# Motor3.net
KiCad netlist of a schematic drawn in Altium Designer
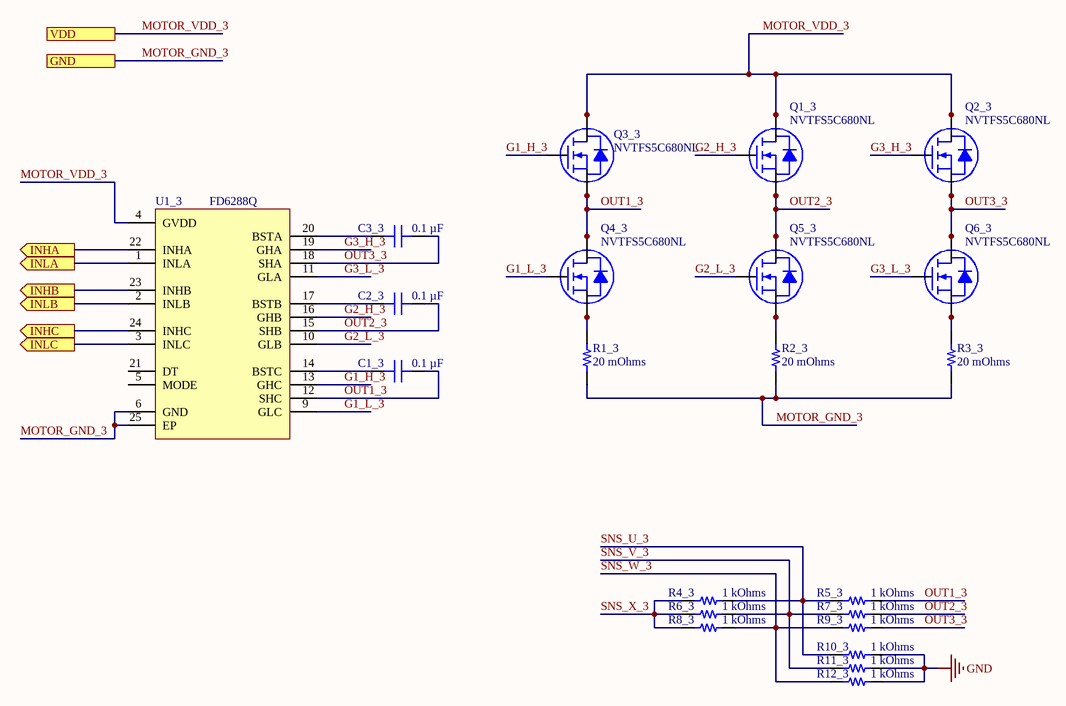
[diagram p0: Motor3.SchDoc]

(export (version "E")
  (design (tool "Eeschema 10.0.6"))
  (components
    (comp (ref "C1_3")
      (value "0.1 µF")
      (footprint "CAP 0402_1005")
      (description "CAP CER 0.1UF 16V X7R 0402")
      (fields (field (name "PART NUMBER") "C0402C104K4RACAUTO") (field (name "MANUFACTURER") "KEMET"))
      (libsource (lib "Celestial Altium Library - altium_library") (part "Capacitor"))
    )
    (comp (ref "C2_3")
      (value "0.1 µF")
      (footprint "CAP 0402_1005")
      (description "CAP CER 0.1UF 16V X7R 0402")
      (fields (field (name "PART NUMBER") "C0402C104K4RACAUTO") (field (name "MANUFACTURER") "KEMET"))
      (libsource (lib "Celestial Altium Library - altium_library") (part "Capacitor"))
    )
    (comp (ref "C3_3")
      (value "0.1 µF")
      (footprint "CAP 0402_1005")
      (description "CAP CER 0.1UF 16V X7R 0402")
      (fields (field (name "PART NUMBER") "C0402C104K4RACAUTO") (field (name "MANUFACTURER") "KEMET"))
      (libsource (lib "Celestial Altium Library - altium_library") (part "Capacitor"))
    )
    (comp (ref "Q1_3")
      (value "NVTFS5C680NL")
      (footprint "NVTFS015N04CTAG")
      (description "N-FET")
      (libsource (lib "IC") (part "NVTFS5C680NL"))
    )
    (comp (ref "Q2_3")
      (value "NVTFS5C680NL")
      (footprint "NVTFS015N04CTAG")
      (description "N-FET")
      (libsource (lib "IC") (part "NVTFS5C680NL"))
    )
    (comp (ref "Q3_3")
      (value "NVTFS5C680NL")
      (footprint "NVTFS015N04CTAG")
      (description "N-FET")
      (libsource (lib "IC") (part "NVTFS5C680NL"))
    )
    (comp (ref "Q4_3")
      (value "NVTFS5C680NL")
      (footprint "NVTFS015N04CTAG")
      (description "N-FET")
      (libsource (lib "IC") (part "NVTFS5C680NL"))
    )
    (comp (ref "Q5_3")
      (value "NVTFS5C680NL")
      (footprint "NVTFS015N04CTAG")
      (description "N-FET")
      (libsource (lib "IC") (part "NVTFS5C680NL"))
    )
    (comp (ref "Q6_3")
      (value "NVTFS5C680NL")
      (footprint "NVTFS015N04CTAG")
      (description "N-FET")
      (libsource (lib "IC") (part "NVTFS5C680NL"))
    )
    (comp (ref "R1_3")
      (value "20 mOhms")
      (footprint "STACKPOLE CSR0805")
      (description "RES 0.02 OHM 1% 1/3W 0603")
      (fields
        (field (name "PART NUMBER") "ERJ-3BWFR020V")
        (field (name "MANUFACTURER") "Panasonic Electronic Components")
      )
      (libsource (lib "Celestial Altium Library - altium_library") (part "Resistor"))
    )
    (comp (ref "R2_3")
      (value "20 mOhms")
      (footprint "STACKPOLE CSR0805")
      (description "RES 0.02 OHM 1% 1/3W 0603")
      (fields
        (field (name "PART NUMBER") "ERJ-3BWFR020V")
        (field (name "MANUFACTURER") "Panasonic Electronic Components")
      )
      (libsource (lib "Celestial Altium Library - altium_library") (part "Resistor"))
    )
    (comp (ref "R3_3")
      (value "20 mOhms")
      (footprint "STACKPOLE CSR0805")
      (description "RES 0.02 OHM 1% 1/3W 0603")
      (fields
        (field (name "PART NUMBER") "ERJ-3BWFR020V")
        (field (name "MANUFACTURER") "Panasonic Electronic Components")
      )
      (libsource (lib "Celestial Altium Library - altium_library") (part "Resistor"))
    )
    (comp (ref "R4_3")
      (value "1 kOhms")
      (footprint "RES 0402_1005")
      (description "RES 14.3K OHM 1% 1/10W 0402")
      (fields
        (field (name "PART NUMBER") "RK73H1ETTP1432F")
        (field (name "MANUFACTURER") "KOA Speer Electronics, Inc.")
      )
      (libsource (lib "Celestial Altium Library - altium_library") (part "Resistor"))
    )
    (comp (ref "R5_3")
      (value "1 kOhms")
      (footprint "RES 0402_1005")
      (description "RES 14.3K OHM 1% 1/10W 0402")
      (fields
        (field (name "PART NUMBER") "RK73H1ETTP1432F")
        (field (name "MANUFACTURER") "KOA Speer Electronics, Inc.")
      )
      (libsource (lib "Celestial Altium Library - altium_library") (part "Resistor"))
    )
    (comp (ref "R6_3")
      (value "1 kOhms")
      (footprint "RES 0402_1005")
      (description "RES 14.3K OHM 1% 1/10W 0402")
      (fields
        (field (name "PART NUMBER") "RK73H1ETTP1432F")
        (field (name "MANUFACTURER") "KOA Speer Electronics, Inc.")
      )
      (libsource (lib "Celestial Altium Library - altium_library") (part "Resistor"))
    )
    (comp (ref "R7_3")
      (value "1 kOhms")
      (footprint "RES 0402_1005")
      (description "RES 14.3K OHM 1% 1/10W 0402")
      (fields
        (field (name "PART NUMBER") "RK73H1ETTP1432F")
        (field (name "MANUFACTURER") "KOA Speer Electronics, Inc.")
      )
      (libsource (lib "Celestial Altium Library - altium_library") (part "Resistor"))
    )
    (comp (ref "R8_3")
      (value "1 kOhms")
      (footprint "RES 0402_1005")
      (description "RES 14.3K OHM 1% 1/10W 0402")
      (fields
        (field (name "PART NUMBER") "RK73H1ETTP1432F")
        (field (name "MANUFACTURER") "KOA Speer Electronics, Inc.")
      )
      (libsource (lib "Celestial Altium Library - altium_library") (part "Resistor"))
    )
    (comp (ref "R9_3")
      (value "1 kOhms")
      (footprint "RES 0402_1005")
      (description "RES 14.3K OHM 1% 1/10W 0402")
      (fields
        (field (name "PART NUMBER") "RK73H1ETTP1432F")
        (field (name "MANUFACTURER") "KOA Speer Electronics, Inc.")
      )
      (libsource (lib "Celestial Altium Library - altium_library") (part "Resistor"))
    )
    (comp (ref "R10_3")
      (value "1 kOhms")
      (footprint "RES 0402_1005")
      (description "RES 14.3K OHM 1% 1/10W 0402")
      (fields
        (field (name "PART NUMBER") "RK73H1ETTP1432F")
        (field (name "MANUFACTURER") "KOA Speer Electronics, Inc.")
      )
      (libsource (lib "Celestial Altium Library - altium_library") (part "Resistor"))
    )
    (comp (ref "R11_3")
      (value "1 kOhms")
      (footprint "RES 0402_1005")
      (description "RES 14.3K OHM 1% 1/10W 0402")
      (fields
        (field (name "PART NUMBER") "RK73H1ETTP1432F")
        (field (name "MANUFACTURER") "KOA Speer Electronics, Inc.")
      )
      (libsource (lib "Celestial Altium Library - altium_library") (part "Resistor"))
    )
    (comp (ref "R12_3")
      (value "1 kOhms")
      (footprint "RES 0402_1005")
      (description "RES 14.3K OHM 1% 1/10W 0402")
      (fields
        (field (name "PART NUMBER") "RK73H1ETTP1432F")
        (field (name "MANUFACTURER") "KOA Speer Electronics, Inc.")
      )
      (libsource (lib "Celestial Altium Library - altium_library") (part "Resistor"))
    )
    (comp (ref "U1_3")
      (value "FD6288Q")
      (footprint "QFN50P400X400X100-25N")
      (description "3 Phase Gate Driver 1.5-2.2A")
      (fields (field (name "MF") "Texas Instruments") (field (name "MP") "UCC27282DRCR"))
      (libsource (lib "IC") (part "FD6288Q"))
    )
  )
  (nets
    (net (code "1") (name "/G1_H_3") (class "Default")
      (node (ref "Q3_3") (pin "4") (pinfunction "G_4") (pintype "passive"))
      (node (ref "U1_3") (pin "13") (pinfunction "GHC_13") (pintype "passive"))
    )
    (net (code "2") (name "/G1_L_3") (class "Default")
      (node (ref "Q4_3") (pin "4") (pinfunction "G_4") (pintype "passive"))
      (node (ref "U1_3") (pin "9") (pinfunction "GLC_9") (pintype "passive"))
    )
    (net (code "3") (name "/G2_H_3") (class "Default")
      (node (ref "Q1_3") (pin "4") (pinfunction "G_4") (pintype "passive"))
      (node (ref "U1_3") (pin "16") (pinfunction "GHB_16") (pintype "passive"))
    )
    (net (code "4") (name "/G2_L_3") (class "Default")
      (node (ref "Q5_3") (pin "4") (pinfunction "G_4") (pintype "passive"))
      (node (ref "U1_3") (pin "10") (pinfunction "GLB_10") (pintype "passive"))
    )
    (net (code "5") (name "/G3_H_3") (class "Default")
      (node (ref "Q2_3") (pin "4") (pinfunction "G_4") (pintype "passive"))
      (node (ref "U1_3") (pin "19") (pinfunction "GHA_19") (pintype "passive"))
    )
    (net (code "6") (name "/G3_L_3") (class "Default")
      (node (ref "Q6_3") (pin "4") (pinfunction "G_4") (pintype "passive"))
      (node (ref "U1_3") (pin "11") (pinfunction "GLA_11") (pintype "passive"))
    )
    (net (code "7") (name "/INHA") (class "Default")
      (node (ref "U1_3") (pin "22") (pinfunction "INHA_22") (pintype "passive"))
    )
    (net (code "8") (name "/INHB") (class "Default")
      (node (ref "U1_3") (pin "23") (pinfunction "INHB_23") (pintype "passive"))
    )
    (net (code "9") (name "/INHC") (class "Default")
      (node (ref "U1_3") (pin "24") (pinfunction "INHC_24") (pintype "passive"))
    )
    (net (code "10") (name "/INLA") (class "Default")
      (node (ref "U1_3") (pin "1") (pinfunction "INLA_1") (pintype "passive"))
    )
    (net (code "11") (name "/INLB") (class "Default")
      (node (ref "U1_3") (pin "2") (pinfunction "INLB_2") (pintype "passive"))
    )
    (net (code "12") (name "/INLC") (class "Default")
      (node (ref "U1_3") (pin "3") (pinfunction "INLC_3") (pintype "passive"))
    )
    (net (code "13") (name "/MOTOR_VDD_3") (class "Default")
      (node (ref "Q1_3") (pin "5") (pinfunction "D_5") (pintype "passive"))
      (node (ref "Q1_3") (pin "6") (pinfunction "D_6") (pintype "passive"))
      (node (ref "Q1_3") (pin "7") (pinfunction "D_7") (pintype "passive"))
      (node (ref "Q1_3") (pin "8") (pinfunction "D_8") (pintype "passive"))
      (node (ref "Q2_3") (pin "5") (pinfunction "D_5") (pintype "passive"))
      (node (ref "Q2_3") (pin "6") (pinfunction "D_6") (pintype "passive"))
      (node (ref "Q2_3") (pin "7") (pinfunction "D_7") (pintype "passive"))
      (node (ref "Q2_3") (pin "8") (pinfunction "D_8") (pintype "passive"))
      (node (ref "Q3_3") (pin "5") (pinfunction "D_5") (pintype "passive"))
      (node (ref "Q3_3") (pin "6") (pinfunction "D_6") (pintype "passive"))
      (node (ref "Q3_3") (pin "7") (pinfunction "D_7") (pintype "passive"))
      (node (ref "Q3_3") (pin "8") (pinfunction "D_8") (pintype "passive"))
      (node (ref "U1_3") (pin "4") (pinfunction "GVDD_4") (pintype "passive"))
    )
    (net (code "14") (name "/OUT1_3") (class "Default")
      (node (ref "C1_3") (pin "2") (pinfunction "2_2") (pintype "passive"))
      (node (ref "Q3_3") (pin "1") (pinfunction "S_1") (pintype "passive"))
      (node (ref "Q3_3") (pin "2") (pinfunction "S_2") (pintype "passive"))
      (node (ref "Q3_3") (pin "3") (pinfunction "S_3") (pintype "passive"))
      (node (ref "Q4_3") (pin "5") (pinfunction "D_5") (pintype "passive"))
      (node (ref "Q4_3") (pin "6") (pinfunction "D_6") (pintype "passive"))
      (node (ref "Q4_3") (pin "7") (pinfunction "D_7") (pintype "passive"))
      (node (ref "Q4_3") (pin "8") (pinfunction "D_8") (pintype "passive"))
      (node (ref "R5_3") (pin "2") (pinfunction "2_2") (pintype "passive"))
      (node (ref "U1_3") (pin "12") (pinfunction "SHC_12") (pintype "passive"))
    )
    (net (code "15") (name "/OUT2_3") (class "Default")
      (node (ref "C2_3") (pin "2") (pinfunction "2_2") (pintype "passive"))
      (node (ref "Q1_3") (pin "1") (pinfunction "S_1") (pintype "passive"))
      (node (ref "Q1_3") (pin "2") (pinfunction "S_2") (pintype "passive"))
      (node (ref "Q1_3") (pin "3") (pinfunction "S_3") (pintype "passive"))
      (node (ref "Q5_3") (pin "5") (pinfunction "D_5") (pintype "passive"))
      (node (ref "Q5_3") (pin "6") (pinfunction "D_6") (pintype "passive"))
      (node (ref "Q5_3") (pin "7") (pinfunction "D_7") (pintype "passive"))
      (node (ref "Q5_3") (pin "8") (pinfunction "D_8") (pintype "passive"))
      (node (ref "R7_3") (pin "2") (pinfunction "2_2") (pintype "passive"))
      (node (ref "U1_3") (pin "15") (pinfunction "SHB_15") (pintype "passive"))
    )
    (net (code "16") (name "/OUT3_3") (class "Default")
      (node (ref "C3_3") (pin "2") (pinfunction "2_2") (pintype "passive"))
      (node (ref "Q2_3") (pin "1") (pinfunction "S_1") (pintype "passive"))
      (node (ref "Q2_3") (pin "2") (pinfunction "S_2") (pintype "passive"))
      (node (ref "Q2_3") (pin "3") (pinfunction "S_3") (pintype "passive"))
      (node (ref "Q6_3") (pin "5") (pinfunction "D_5") (pintype "passive"))
      (node (ref "Q6_3") (pin "6") (pinfunction "D_6") (pintype "passive"))
      (node (ref "Q6_3") (pin "7") (pinfunction "D_7") (pintype "passive"))
      (node (ref "Q6_3") (pin "8") (pinfunction "D_8") (pintype "passive"))
      (node (ref "R9_3") (pin "2") (pinfunction "2_2") (pintype "passive"))
      (node (ref "U1_3") (pin "18") (pinfunction "SHA_18") (pintype "passive"))
    )
    (net (code "17") (name "/SNS_U_3") (class "Default")
      (node (ref "R10_3") (pin "2") (pinfunction "2_2") (pintype "passive"))
      (node (ref "R4_3") (pin "2") (pinfunction "2_2") (pintype "passive"))
      (node (ref "R5_3") (pin "1") (pinfunction "1_1") (pintype "passive"))
    )
    (net (code "18") (name "/SNS_V_3") (class "Default")
      (node (ref "R11_3") (pin "2") (pinfunction "2_2") (pintype "passive"))
      (node (ref "R6_3") (pin "2") (pinfunction "2_2") (pintype "passive"))
      (node (ref "R7_3") (pin "1") (pinfunction "1_1") (pintype "passive"))
    )
    (net (code "19") (name "/SNS_W_3") (class "Default")
      (node (ref "R12_3") (pin "2") (pinfunction "2_2") (pintype "passive"))
      (node (ref "R8_3") (pin "2") (pinfunction "2_2") (pintype "passive"))
      (node (ref "R9_3") (pin "1") (pinfunction "1_1") (pintype "passive"))
    )
    (net (code "20") (name "/SNS_X_3") (class "Default")
      (node (ref "R4_3") (pin "1") (pinfunction "1_1") (pintype "passive"))
      (node (ref "R6_3") (pin "1") (pinfunction "1_1") (pintype "passive"))
      (node (ref "R8_3") (pin "1") (pinfunction "1_1") (pintype "passive"))
    )
    (net (code "21") (name "GND") (class "Default")
      (node (ref "R10_3") (pin "1") (pinfunction "1_1") (pintype "passive"))
      (node (ref "R11_3") (pin "1") (pinfunction "1_1") (pintype "passive"))
      (node (ref "R12_3") (pin "1") (pinfunction "1_1") (pintype "passive"))
      (node (ref "R1_3") (pin "1") (pinfunction "1_1") (pintype "passive"))
      (node (ref "R2_3") (pin "1") (pinfunction "1_1") (pintype "passive"))
      (node (ref "R3_3") (pin "1") (pinfunction "1_1") (pintype "passive"))
      (node (ref "U1_3") (pin "25") (pinfunction "EP_25") (pintype "passive"))
      (node (ref "U1_3") (pin "6") (pinfunction "GND_6") (pintype "passive"))
    )
    (net (code "22") (name "Net-(Q4_3-S-Pad1)") (class "Default")
      (node (ref "Q4_3") (pin "1") (pinfunction "S_1") (pintype "passive"))
      (node (ref "Q4_3") (pin "2") (pinfunction "S_2") (pintype "passive"))
      (node (ref "Q4_3") (pin "3") (pinfunction "S_3") (pintype "passive"))
      (node (ref "R1_3") (pin "2") (pinfunction "2_2") (pintype "passive"))
    )
    (net (code "23") (name "Net-(Q5_3-S-Pad1)") (class "Default")
      (node (ref "Q5_3") (pin "1") (pinfunction "S_1") (pintype "passive"))
      (node (ref "Q5_3") (pin "2") (pinfunction "S_2") (pintype "passive"))
      (node (ref "Q5_3") (pin "3") (pinfunction "S_3") (pintype "passive"))
      (node (ref "R2_3") (pin "2") (pinfunction "2_2") (pintype "passive"))
    )
    (net (code "24") (name "Net-(Q6_3-S-Pad1)") (class "Default")
      (node (ref "Q6_3") (pin "1") (pinfunction "S_1") (pintype "passive"))
      (node (ref "Q6_3") (pin "2") (pinfunction "S_2") (pintype "passive"))
      (node (ref "Q6_3") (pin "3") (pinfunction "S_3") (pintype "passive"))
      (node (ref "R3_3") (pin "2") (pinfunction "2_2") (pintype "passive"))
    )
    (net (code "25") (name "Net-(U1_3-BSTA)") (class "Default")
      (node (ref "C3_3") (pin "1") (pinfunction "1_1") (pintype "passive"))
      (node (ref "U1_3") (pin "20") (pinfunction "BSTA_20") (pintype "passive"))
    )
    (net (code "26") (name "Net-(U1_3-BSTB)") (class "Default")
      (node (ref "C2_3") (pin "1") (pinfunction "1_1") (pintype "passive"))
      (node (ref "U1_3") (pin "17") (pinfunction "BSTB_17") (pintype "passive"))
    )
    (net (code "27") (name "Net-(U1_3-BSTC)") (class "Default")
      (node (ref "C1_3") (pin "1") (pinfunction "1_1") (pintype "passive"))
      (node (ref "U1_3") (pin "14") (pinfunction "BSTC_14") (pintype "passive"))
    )
    (net (code "28") (name "unconnected-(U1_3-DT-Pad21)") (class "Default")
      (node (ref "U1_3") (pin "21") (pinfunction "DT_21") (pintype "passive"))
    )
    (net (code "29") (name "unconnected-(U1_3-MODE-Pad5)") (class "Default")
      (node (ref "U1_3") (pin "5") (pinfunction "MODE_5") (pintype "passive"))
    )
  )
)
